# 83_SATA-SATA_PM1.net
KiCad netlist of a schematic drawn in Altium Designer
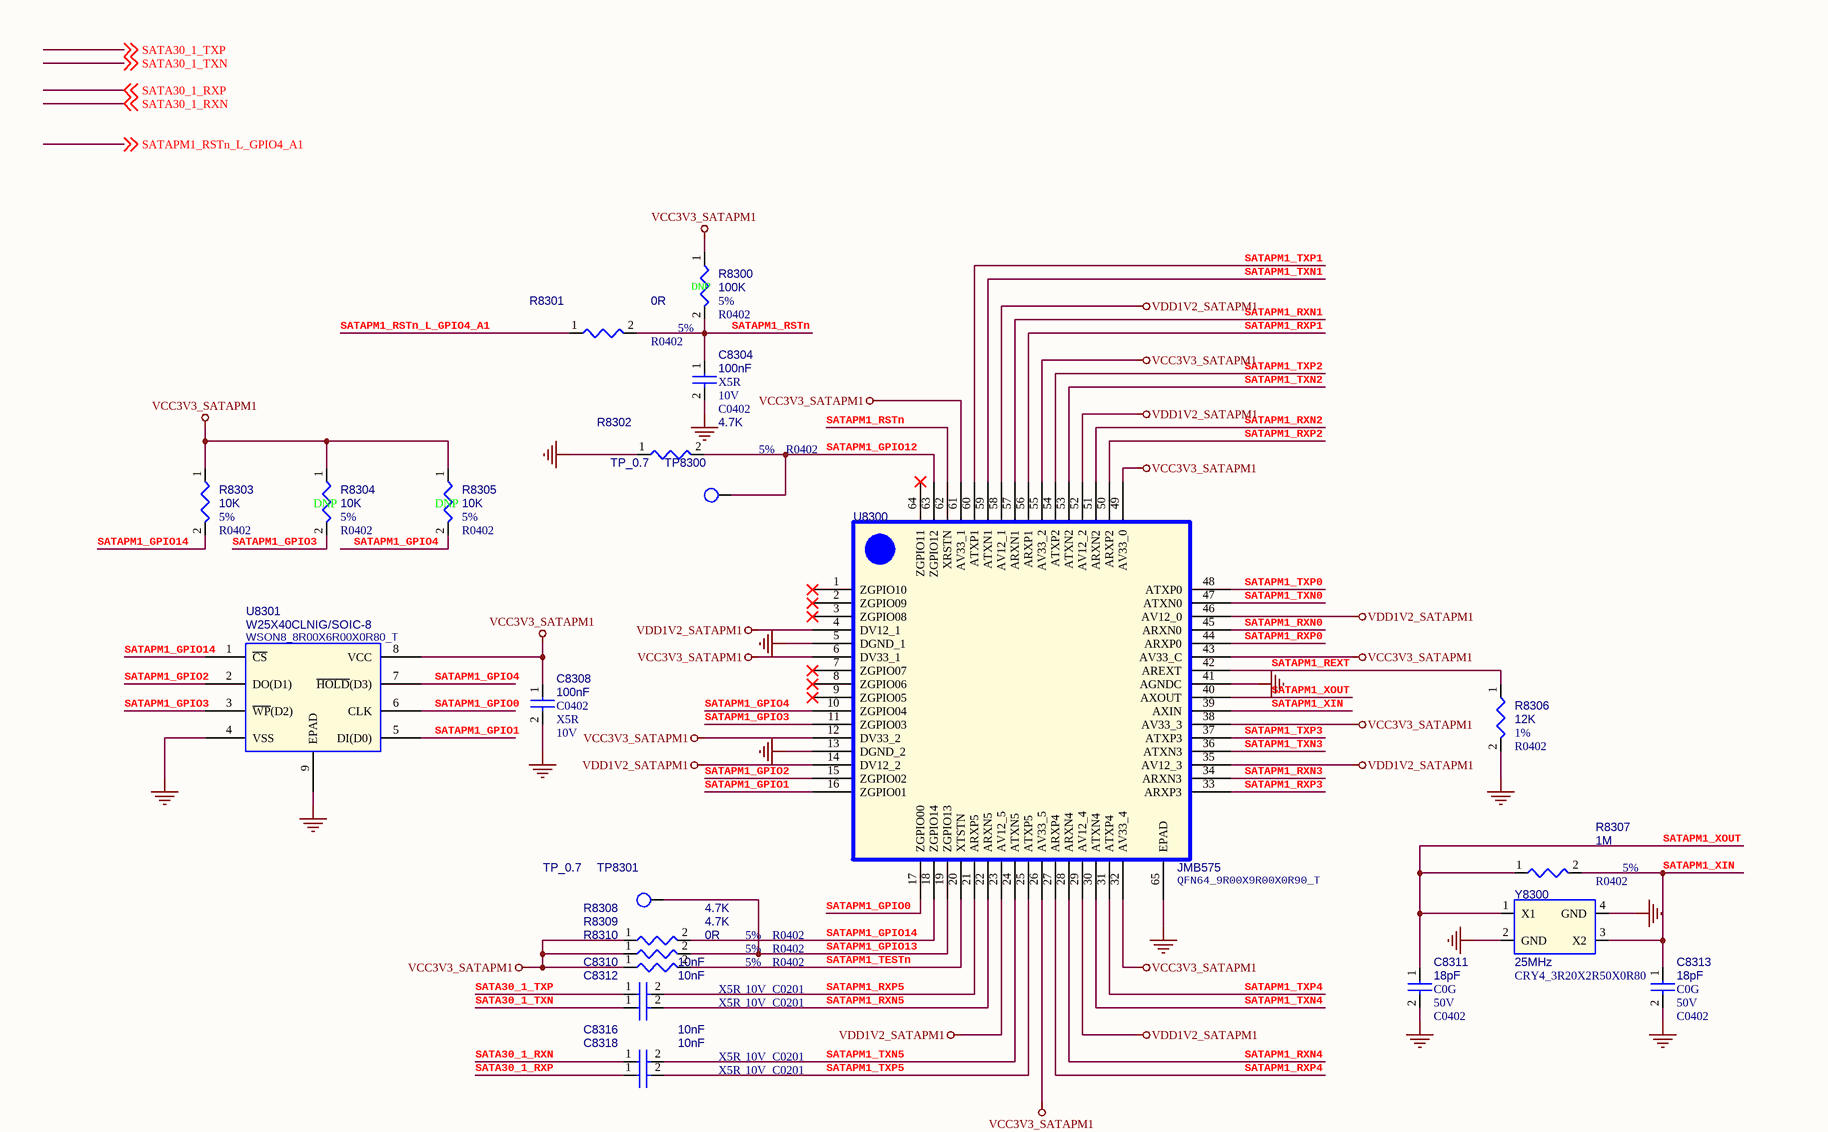
[diagram p0: 83.SATA-SATA PM1.SchDoc, top left]
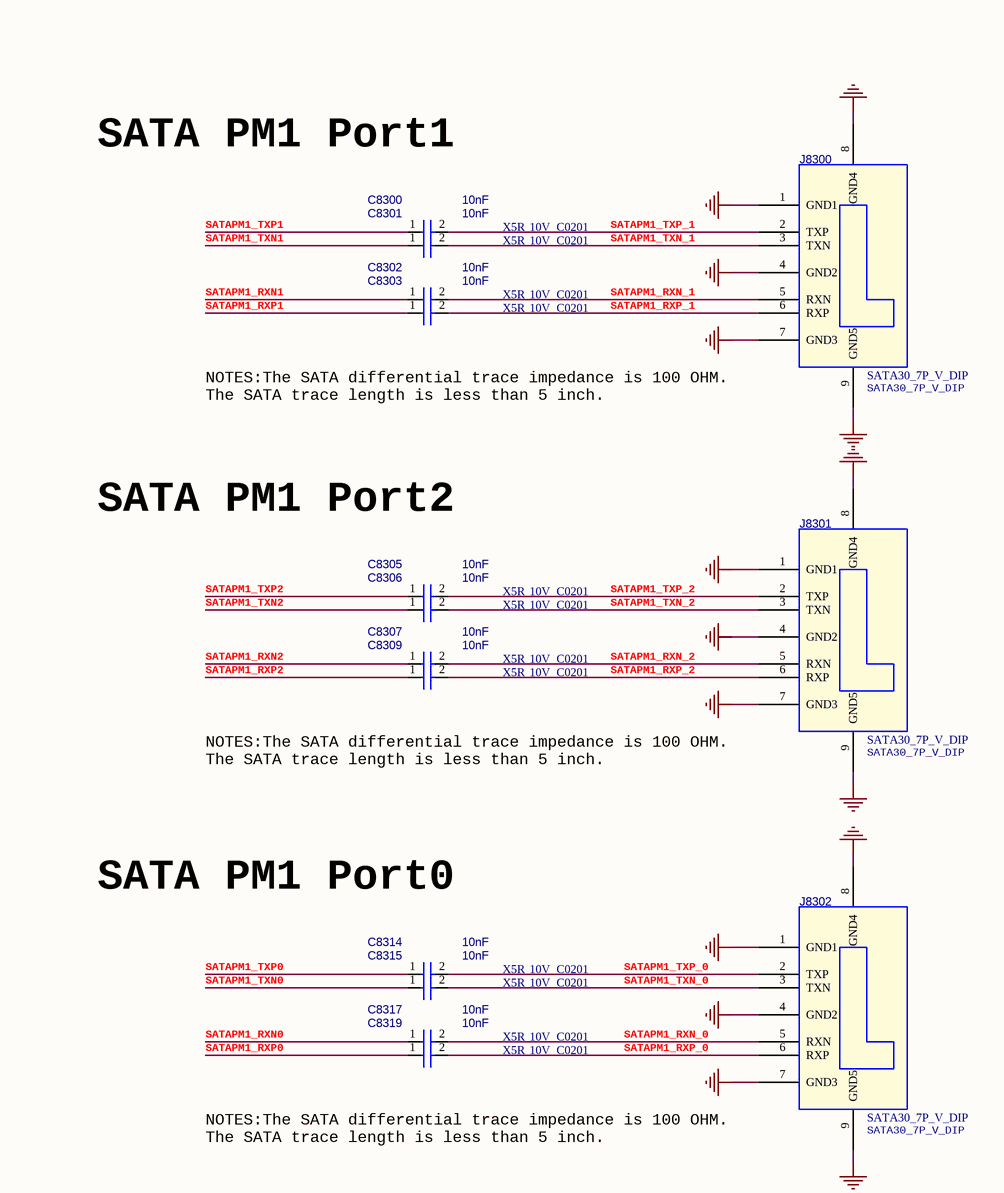
[diagram p1: 83.SATA-SATA PM1.SchDoc, top right]
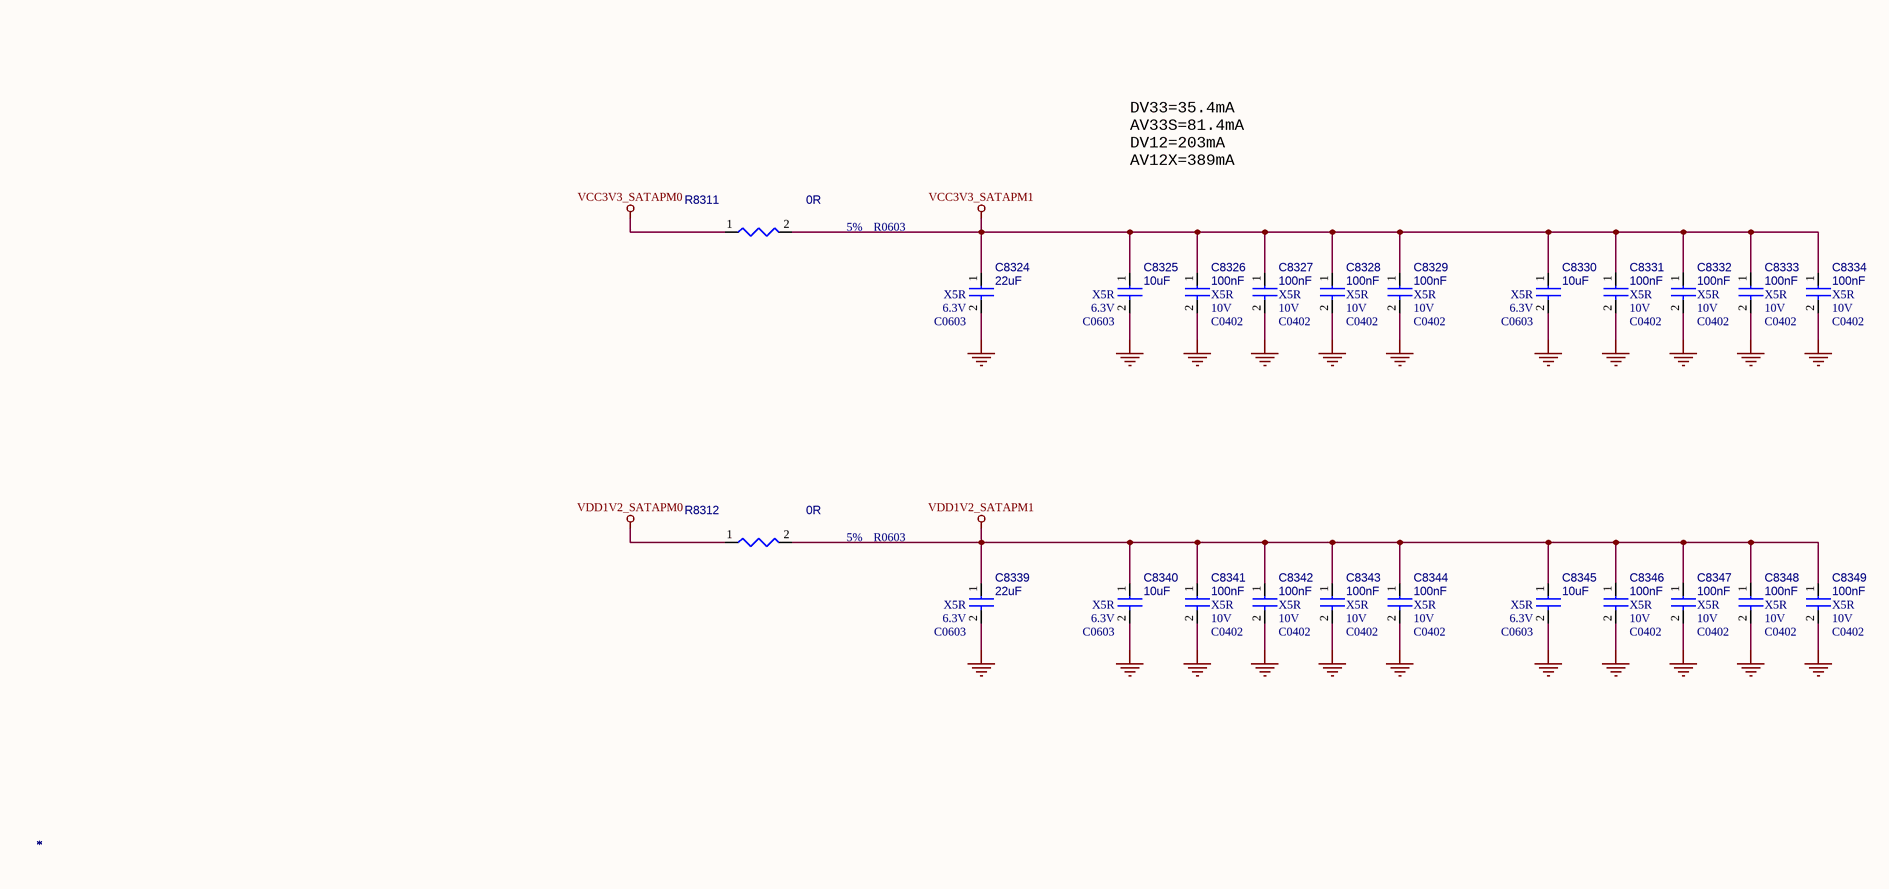
[diagram p2: 83.SATA-SATA PM1.SchDoc, bottom left]
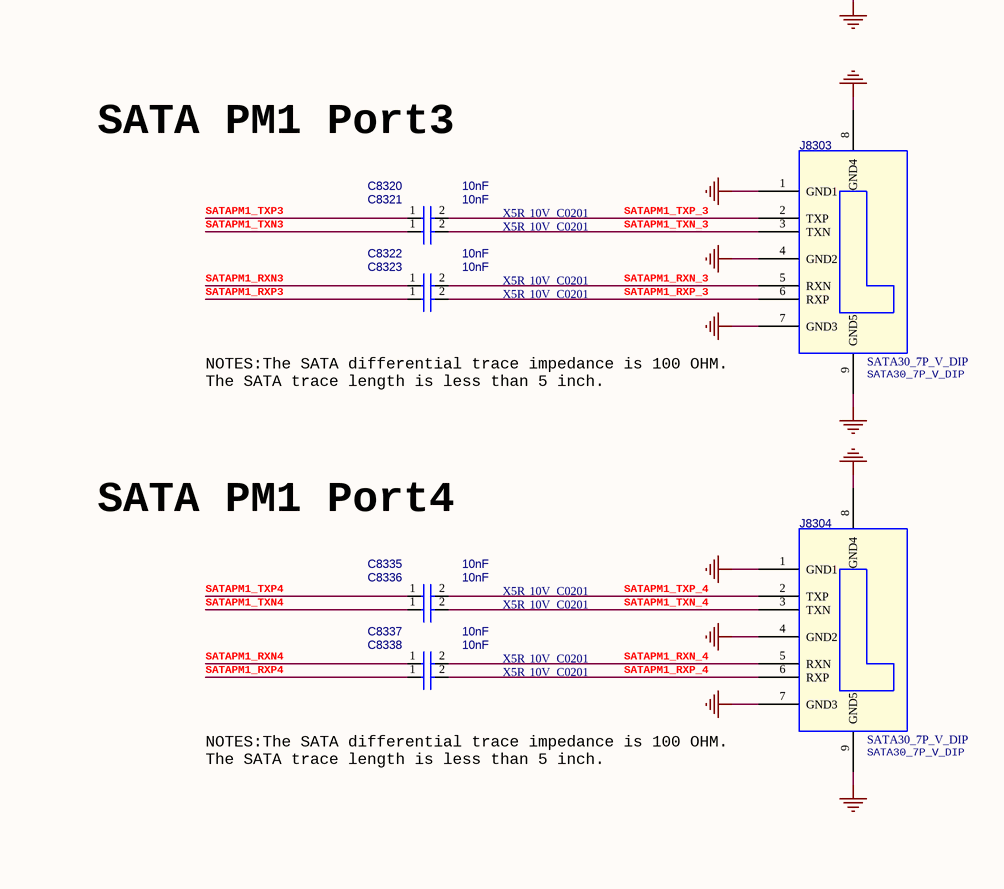
[diagram p3: 83.SATA-SATA PM1.SchDoc, bottom right]

(export (version "E")
  (design (tool "Eeschema 10.0.6"))
  (components
    (comp (ref "C8300")
      (value "*")
      (footprint "C0201")
      (description "cap,10.00nF,+/-10%,10V,X5R,C0201")
      (fields
        (field (name "VOLTAGE") "10V")
        (field (name "PCB FOOTPRINT") "C0201")
        (field (name "DIELECTRIC") "X5R")
        (field (name "MANUFACTURER") "TDK")
        (field (name "TOLERANCE") "10%")
        (field (name "ALTIUM_UNNAMED_1") "10nF")
        (field (name "CREATED BY") "JJJ")
      )
      (libsource (lib "*") (part "CAP NP"))
    )
    (comp (ref "C8301")
      (value "*")
      (footprint "C0201")
      (description "cap,10.00nF,+/-10%,10V,X5R,C0201")
      (fields
        (field (name "VOLTAGE") "10V")
        (field (name "PCB FOOTPRINT") "C0201")
        (field (name "DIELECTRIC") "X5R")
        (field (name "MANUFACTURER") "TDK")
        (field (name "TOLERANCE") "10%")
        (field (name "ALTIUM_UNNAMED_1") "10nF")
        (field (name "CREATED BY") "JJJ")
      )
      (libsource (lib "*") (part "CAP NP"))
    )
    (comp (ref "C8302")
      (value "*")
      (footprint "C0201")
      (description "cap,10.00nF,+/-10%,10V,X5R,C0201")
      (fields
        (field (name "VOLTAGE") "10V")
        (field (name "PCB FOOTPRINT") "C0201")
        (field (name "DIELECTRIC") "X5R")
        (field (name "MANUFACTURER") "TDK")
        (field (name "TOLERANCE") "10%")
        (field (name "ALTIUM_UNNAMED_1") "10nF")
        (field (name "CREATED BY") "JJJ")
      )
      (libsource (lib "*") (part "CAP NP"))
    )
    (comp (ref "C8303")
      (value "*")
      (footprint "C0201")
      (description "cap,10.00nF,+/-10%,10V,X5R,C0201")
      (fields
        (field (name "VOLTAGE") "10V")
        (field (name "PCB FOOTPRINT") "C0201")
        (field (name "DIELECTRIC") "X5R")
        (field (name "MANUFACTURER") "TDK")
        (field (name "TOLERANCE") "10%")
        (field (name "ALTIUM_UNNAMED_1") "10nF")
        (field (name "CREATED BY") "JJJ")
      )
      (libsource (lib "*") (part "CAP NP"))
    )
    (comp (ref "C8304")
      (value "*")
      (footprint "C0402")
      (description "cap,100.00nF,+/-10%,10V,X5R,C0402")
      (fields
        (field (name "VOLTAGE") "10V")
        (field (name "PCB FOOTPRINT") "C0402")
        (field (name "DIELECTRIC") "X5R")
        (field (name "TOLERANCE") "10%")
        (field (name "MANUFACTURER") "TDK")
        (field (name "ALTIUM_UNNAMED_1") "100nF")
        (field (name "CREATED BY") "JJJ")
      )
      (libsource (lib "*") (part "CAP NP"))
    )
    (comp (ref "C8305")
      (value "*")
      (footprint "C0201")
      (description "cap,10.00nF,+/-10%,10V,X5R,C0201")
      (fields
        (field (name "VOLTAGE") "10V")
        (field (name "PCB FOOTPRINT") "C0201")
        (field (name "DIELECTRIC") "X5R")
        (field (name "MANUFACTURER") "TDK")
        (field (name "TOLERANCE") "10%")
        (field (name "ALTIUM_UNNAMED_1") "10nF")
        (field (name "CREATED BY") "JJJ")
      )
      (libsource (lib "*") (part "CAP NP"))
    )
    (comp (ref "C8306")
      (value "*")
      (footprint "C0201")
      (description "cap,10.00nF,+/-10%,10V,X5R,C0201")
      (fields
        (field (name "VOLTAGE") "10V")
        (field (name "PCB FOOTPRINT") "C0201")
        (field (name "DIELECTRIC") "X5R")
        (field (name "MANUFACTURER") "TDK")
        (field (name "TOLERANCE") "10%")
        (field (name "ALTIUM_UNNAMED_1") "10nF")
        (field (name "CREATED BY") "JJJ")
      )
      (libsource (lib "*") (part "CAP NP"))
    )
    (comp (ref "C8307")
      (value "*")
      (footprint "C0201")
      (description "cap,10.00nF,+/-10%,10V,X5R,C0201")
      (fields
        (field (name "VOLTAGE") "10V")
        (field (name "PCB FOOTPRINT") "C0201")
        (field (name "DIELECTRIC") "X5R")
        (field (name "MANUFACTURER") "TDK")
        (field (name "TOLERANCE") "10%")
        (field (name "ALTIUM_UNNAMED_1") "10nF")
        (field (name "CREATED BY") "JJJ")
      )
      (libsource (lib "*") (part "CAP NP"))
    )
    (comp (ref "C8308")
      (value "*")
      (footprint "C0402")
      (description "cap,100.00nF,+/-10%,10V,X5R,C0402")
      (fields
        (field (name "VOLTAGE") "10V")
        (field (name "PCB FOOTPRINT") "C0402")
        (field (name "DIELECTRIC") "X5R")
        (field (name "TOLERANCE") "10%")
        (field (name "MANUFACTURER") "TDK")
        (field (name "ALTIUM_UNNAMED_1") "100nF")
        (field (name "CREATED BY") "JJJ")
      )
      (libsource (lib "*") (part "CAP NP"))
    )
    (comp (ref "C8309")
      (value "*")
      (footprint "C0201")
      (description "cap,10.00nF,+/-10%,10V,X5R,C0201")
      (fields
        (field (name "VOLTAGE") "10V")
        (field (name "PCB FOOTPRINT") "C0201")
        (field (name "DIELECTRIC") "X5R")
        (field (name "MANUFACTURER") "TDK")
        (field (name "TOLERANCE") "10%")
        (field (name "ALTIUM_UNNAMED_1") "10nF")
        (field (name "CREATED BY") "JJJ")
      )
      (libsource (lib "*") (part "CAP NP"))
    )
    (comp (ref "C8310")
      (value "*")
      (footprint "C0201")
      (description "cap,10.00nF,+/-10%,10V,X5R,C0201")
      (fields
        (field (name "VOLTAGE") "10V")
        (field (name "PCB FOOTPRINT") "C0201")
        (field (name "DIELECTRIC") "X5R")
        (field (name "TOLERANCE") "10%")
        (field (name "MANUFACTURER") "TDK")
        (field (name "ALTIUM_UNNAMED_1") "10nF")
        (field (name "CREATED BY") "JJJ")
      )
      (libsource (lib "*") (part "CAP NP"))
    )
    (comp (ref "C8311")
      (value "*")
      (footprint "C0402")
      (description "cap,18.00pF,+/-5%,50V,C0G,C0402")
      (fields
        (field (name "VOLTAGE") "50V")
        (field (name "PCB FOOTPRINT") "C0402")
        (field (name "DIELECTRIC") "C0G")
        (field (name "TOLERANCE") "5%")
        (field (name "MANUFACTURER") "TDK")
        (field (name "ALTIUM_UNNAMED_1") "18pF")
        (field (name "CREATED BY") "JJJ")
      )
      (libsource (lib "*") (part "CAP NP"))
    )
    (comp (ref "C8312")
      (value "*")
      (footprint "C0201")
      (description "cap,10.00nF,+/-10%,10V,X5R,C0201")
      (fields
        (field (name "VOLTAGE") "10V")
        (field (name "PCB FOOTPRINT") "C0201")
        (field (name "DIELECTRIC") "X5R")
        (field (name "TOLERANCE") "10%")
        (field (name "MANUFACTURER") "TDK")
        (field (name "ALTIUM_UNNAMED_1") "10nF")
        (field (name "CREATED BY") "JJJ")
      )
      (libsource (lib "*") (part "CAP NP"))
    )
    (comp (ref "C8313")
      (value "*")
      (footprint "C0402")
      (description "cap,18.00pF,+/-5%,50V,C0G,C0402")
      (fields
        (field (name "VOLTAGE") "50V")
        (field (name "PCB FOOTPRINT") "C0402")
        (field (name "DIELECTRIC") "C0G")
        (field (name "TOLERANCE") "5%")
        (field (name "MANUFACTURER") "TDK")
        (field (name "ALTIUM_UNNAMED_1") "18pF")
        (field (name "CREATED BY") "JJJ")
      )
      (libsource (lib "*") (part "CAP NP"))
    )
    (comp (ref "C8314")
      (value "*")
      (footprint "C0201")
      (description "cap,10.00nF,+/-10%,10V,X5R,C0201")
      (fields
        (field (name "VOLTAGE") "10V")
        (field (name "PCB FOOTPRINT") "C0201")
        (field (name "DIELECTRIC") "X5R")
        (field (name "MANUFACTURER") "TDK")
        (field (name "TOLERANCE") "10%")
        (field (name "ALTIUM_UNNAMED_1") "10nF")
        (field (name "CREATED BY") "JJJ")
      )
      (libsource (lib "*") (part "CAP NP"))
    )
    (comp (ref "C8315")
      (value "*")
      (footprint "C0201")
      (description "cap,10.00nF,+/-10%,10V,X5R,C0201")
      (fields
        (field (name "VOLTAGE") "10V")
        (field (name "PCB FOOTPRINT") "C0201")
        (field (name "DIELECTRIC") "X5R")
        (field (name "MANUFACTURER") "TDK")
        (field (name "TOLERANCE") "10%")
        (field (name "ALTIUM_UNNAMED_1") "10nF")
        (field (name "CREATED BY") "JJJ")
      )
      (libsource (lib "*") (part "CAP NP"))
    )
    (comp (ref "C8316")
      (value "*")
      (footprint "C0201")
      (description "cap,10.00nF,+/-10%,10V,X5R,C0201")
      (fields
        (field (name "VOLTAGE") "10V")
        (field (name "PCB FOOTPRINT") "C0201")
        (field (name "DIELECTRIC") "X5R")
        (field (name "TOLERANCE") "10%")
        (field (name "MANUFACTURER") "TDK")
        (field (name "ALTIUM_UNNAMED_1") "10nF")
        (field (name "CREATED BY") "JJJ")
      )
      (libsource (lib "*") (part "CAP NP"))
    )
    (comp (ref "C8317")
      (value "*")
      (footprint "C0201")
      (description "cap,10.00nF,+/-10%,10V,X5R,C0201")
      (fields
        (field (name "VOLTAGE") "10V")
        (field (name "PCB FOOTPRINT") "C0201")
        (field (name "DIELECTRIC") "X5R")
        (field (name "MANUFACTURER") "TDK")
        (field (name "TOLERANCE") "10%")
        (field (name "ALTIUM_UNNAMED_1") "10nF")
        (field (name "CREATED BY") "JJJ")
      )
      (libsource (lib "*") (part "CAP NP"))
    )
    (comp (ref "C8318")
      (value "*")
      (footprint "C0201")
      (description "cap,10.00nF,+/-10%,10V,X5R,C0201")
      (fields
        (field (name "VOLTAGE") "10V")
        (field (name "PCB FOOTPRINT") "C0201")
        (field (name "DIELECTRIC") "X5R")
        (field (name "TOLERANCE") "10%")
        (field (name "MANUFACTURER") "TDK")
        (field (name "ALTIUM_UNNAMED_1") "10nF")
        (field (name "CREATED BY") "JJJ")
      )
      (libsource (lib "*") (part "CAP NP"))
    )
    (comp (ref "C8319")
      (value "*")
      (footprint "C0201")
      (description "cap,10.00nF,+/-10%,10V,X5R,C0201")
      (fields
        (field (name "VOLTAGE") "10V")
        (field (name "PCB FOOTPRINT") "C0201")
        (field (name "DIELECTRIC") "X5R")
        (field (name "MANUFACTURER") "TDK")
        (field (name "TOLERANCE") "10%")
        (field (name "ALTIUM_UNNAMED_1") "10nF")
        (field (name "CREATED BY") "JJJ")
      )
      (libsource (lib "*") (part "CAP NP"))
    )
    (comp (ref "C8320")
      (value "*")
      (footprint "C0201")
      (description "cap,10.00nF,+/-10%,10V,X5R,C0201")
      (fields
        (field (name "VOLTAGE") "10V")
        (field (name "PCB FOOTPRINT") "C0201")
        (field (name "DIELECTRIC") "X5R")
        (field (name "MANUFACTURER") "TDK")
        (field (name "TOLERANCE") "10%")
        (field (name "ALTIUM_UNNAMED_1") "10nF")
        (field (name "CREATED BY") "JJJ")
      )
      (libsource (lib "*") (part "CAP NP"))
    )
    (comp (ref "C8321")
      (value "*")
      (footprint "C0201")
      (description "cap,10.00nF,+/-10%,10V,X5R,C0201")
      (fields
        (field (name "VOLTAGE") "10V")
        (field (name "PCB FOOTPRINT") "C0201")
        (field (name "DIELECTRIC") "X5R")
        (field (name "MANUFACTURER") "TDK")
        (field (name "TOLERANCE") "10%")
        (field (name "ALTIUM_UNNAMED_1") "10nF")
        (field (name "CREATED BY") "JJJ")
      )
      (libsource (lib "*") (part "CAP NP"))
    )
    (comp (ref "C8322")
      (value "*")
      (footprint "C0201")
      (description "cap,10.00nF,+/-10%,10V,X5R,C0201")
      (fields
        (field (name "VOLTAGE") "10V")
        (field (name "PCB FOOTPRINT") "C0201")
        (field (name "DIELECTRIC") "X5R")
        (field (name "MANUFACTURER") "TDK")
        (field (name "TOLERANCE") "10%")
        (field (name "ALTIUM_UNNAMED_1") "10nF")
        (field (name "CREATED BY") "JJJ")
      )
      (libsource (lib "*") (part "CAP NP"))
    )
    (comp (ref "C8323")
      (value "*")
      (footprint "C0201")
      (description "cap,10.00nF,+/-10%,10V,X5R,C0201")
      (fields
        (field (name "VOLTAGE") "10V")
        (field (name "PCB FOOTPRINT") "C0201")
        (field (name "DIELECTRIC") "X5R")
        (field (name "MANUFACTURER") "TDK")
        (field (name "TOLERANCE") "10%")
        (field (name "ALTIUM_UNNAMED_1") "10nF")
        (field (name "CREATED BY") "JJJ")
      )
      (libsource (lib "*") (part "CAP NP"))
    )
    (comp (ref "C8324")
      (value "*")
      (footprint "C0603")
      (description "cap,22.00uF,+/-20%,6.3V,X5R,C0603")
      (fields
        (field (name "VOLTAGE") "6.3V")
        (field (name "PCB FOOTPRINT") "C0603")
        (field (name "DIELECTRIC") "X5R")
        (field (name "MANUFACTURER") "TDK")
        (field (name "TOLERANCE") "20%")
        (field (name "ALTIUM_UNNAMED_1") "22uF")
        (field (name "CREATED BY") "JJJ")
      )
      (libsource (lib "*") (part "CAP NP"))
    )
    (comp (ref "C8325")
      (value "*")
      (footprint "C0603")
      (description "cap,10.00uF,+/-10%,6.3V,X5R,C0603")
      (fields
        (field (name "VOLTAGE") "6.3V")
        (field (name "PCB FOOTPRINT") "C0603")
        (field (name "DIELECTRIC") "X5R")
        (field (name "TOLERANCE") "10%")
        (field (name "MANUFACTURER") "TDK")
        (field (name "ALTIUM_UNNAMED_1") "10uF")
        (field (name "CREATED BY") "JJJ")
      )
      (libsource (lib "*") (part "CAP NP"))
    )
    (comp (ref "C8326")
      (value "*")
      (footprint "C0402")
      (description "cap,100.00nF,+/-10%,10V,X5R,C0402")
      (fields
        (field (name "VOLTAGE") "10V")
        (field (name "PCB FOOTPRINT") "C0402")
        (field (name "DIELECTRIC") "X5R")
        (field (name "MANUFACTURER") "TDK")
        (field (name "TOLERANCE") "10%")
        (field (name "ALTIUM_UNNAMED_1") "100nF")
        (field (name "CREATED BY") "JJJ")
      )
      (libsource (lib "*") (part "CAP NP"))
    )
    (comp (ref "C8327")
      (value "*")
      (footprint "C0402")
      (description "cap,100.00nF,+/-10%,10V,X5R,C0402")
      (fields
        (field (name "VOLTAGE") "10V")
        (field (name "PCB FOOTPRINT") "C0402")
        (field (name "DIELECTRIC") "X5R")
        (field (name "MANUFACTURER") "TDK")
        (field (name "TOLERANCE") "10%")
        (field (name "ALTIUM_UNNAMED_1") "100nF")
        (field (name "CREATED BY") "JJJ")
      )
      (libsource (lib "*") (part "CAP NP"))
    )
    (comp (ref "C8328")
      (value "*")
      (footprint "C0402")
      (description "cap,100.00nF,+/-10%,10V,X5R,C0402")
      (fields
        (field (name "VOLTAGE") "10V")
        (field (name "PCB FOOTPRINT") "C0402")
        (field (name "DIELECTRIC") "X5R")
        (field (name "MANUFACTURER") "TDK")
        (field (name "TOLERANCE") "10%")
        (field (name "ALTIUM_UNNAMED_1") "100nF")
        (field (name "CREATED BY") "JJJ")
      )
      (libsource (lib "*") (part "CAP NP"))
    )
    (comp (ref "C8329")
      (value "*")
      (footprint "C0402")
      (description "cap,100.00nF,+/-10%,10V,X5R,C0402")
      (fields
        (field (name "VOLTAGE") "10V")
        (field (name "PCB FOOTPRINT") "C0402")
        (field (name "DIELECTRIC") "X5R")
        (field (name "MANUFACTURER") "TDK")
        (field (name "TOLERANCE") "10%")
        (field (name "ALTIUM_UNNAMED_1") "100nF")
        (field (name "CREATED BY") "JJJ")
      )
      (libsource (lib "*") (part "CAP NP"))
    )
    (comp (ref "C8330")
      (value "*")
      (footprint "C0603")
      (description "cap,10.00uF,+/-10%,6.3V,X5R,C0603")
      (fields
        (field (name "VOLTAGE") "6.3V")
        (field (name "PCB FOOTPRINT") "C0603")
        (field (name "DIELECTRIC") "X5R")
        (field (name "TOLERANCE") "10%")
        (field (name "MANUFACTURER") "TDK")
        (field (name "ALTIUM_UNNAMED_1") "10uF")
        (field (name "CREATED BY") "JJJ")
      )
      (libsource (lib "*") (part "CAP NP"))
    )
    (comp (ref "C8331")
      (value "*")
      (footprint "C0402")
      (description "cap,100.00nF,+/-10%,10V,X5R,C0402")
      (fields
        (field (name "VOLTAGE") "10V")
        (field (name "PCB FOOTPRINT") "C0402")
        (field (name "DIELECTRIC") "X5R")
        (field (name "MANUFACTURER") "TDK")
        (field (name "TOLERANCE") "10%")
        (field (name "ALTIUM_UNNAMED_1") "100nF")
        (field (name "CREATED BY") "JJJ")
      )
      (libsource (lib "*") (part "CAP NP"))
    )
    (comp (ref "C8332")
      (value "*")
      (footprint "C0402")
      (description "cap,100.00nF,+/-10%,10V,X5R,C0402")
      (fields
        (field (name "VOLTAGE") "10V")
        (field (name "PCB FOOTPRINT") "C0402")
        (field (name "DIELECTRIC") "X5R")
        (field (name "MANUFACTURER") "TDK")
        (field (name "TOLERANCE") "10%")
        (field (name "ALTIUM_UNNAMED_1") "100nF")
        (field (name "CREATED BY") "JJJ")
      )
      (libsource (lib "*") (part "CAP NP"))
    )
    (comp (ref "C8333")
      (value "*")
      (footprint "C0402")
      (description "cap,100.00nF,+/-10%,10V,X5R,C0402")
      (fields
        (field (name "VOLTAGE") "10V")
        (field (name "PCB FOOTPRINT") "C0402")
        (field (name "DIELECTRIC") "X5R")
        (field (name "MANUFACTURER") "TDK")
        (field (name "TOLERANCE") "10%")
        (field (name "ALTIUM_UNNAMED_1") "100nF")
        (field (name "CREATED BY") "JJJ")
      )
      (libsource (lib "*") (part "CAP NP"))
    )
    (comp (ref "C8334")
      (value "*")
      (footprint "C0402")
      (description "cap,100.00nF,+/-10%,10V,X5R,C0402")
      (fields
        (field (name "VOLTAGE") "10V")
        (field (name "PCB FOOTPRINT") "C0402")
        (field (name "DIELECTRIC") "X5R")
        (field (name "MANUFACTURER") "TDK")
        (field (name "TOLERANCE") "10%")
        (field (name "ALTIUM_UNNAMED_1") "100nF")
        (field (name "CREATED BY") "JJJ")
      )
      (libsource (lib "*") (part "CAP NP"))
    )
    (comp (ref "C8335")
      (value "*")
      (footprint "C0201")
      (description "cap,10.00nF,+/-10%,10V,X5R,C0201")
      (fields
        (field (name "VOLTAGE") "10V")
        (field (name "PCB FOOTPRINT") "C0201")
        (field (name "DIELECTRIC") "X5R")
        (field (name "MANUFACTURER") "TDK")
        (field (name "TOLERANCE") "10%")
        (field (name "ALTIUM_UNNAMED_1") "10nF")
        (field (name "CREATED BY") "JJJ")
      )
      (libsource (lib "*") (part "CAP NP"))
    )
    (comp (ref "C8336")
      (value "*")
      (footprint "C0201")
      (description "cap,10.00nF,+/-10%,10V,X5R,C0201")
      (fields
        (field (name "VOLTAGE") "10V")
        (field (name "PCB FOOTPRINT") "C0201")
        (field (name "DIELECTRIC") "X5R")
        (field (name "MANUFACTURER") "TDK")
        (field (name "TOLERANCE") "10%")
        (field (name "ALTIUM_UNNAMED_1") "10nF")
        (field (name "CREATED BY") "JJJ")
      )
      (libsource (lib "*") (part "CAP NP"))
    )
    (comp (ref "C8337")
      (value "*")
      (footprint "C0201")
      (description "cap,10.00nF,+/-10%,10V,X5R,C0201")
      (fields
        (field (name "VOLTAGE") "10V")
        (field (name "PCB FOOTPRINT") "C0201")
        (field (name "DIELECTRIC") "X5R")
        (field (name "MANUFACTURER") "TDK")
        (field (name "TOLERANCE") "10%")
        (field (name "ALTIUM_UNNAMED_1") "10nF")
        (field (name "CREATED BY") "JJJ")
      )
      (libsource (lib "*") (part "CAP NP"))
    )
    (comp (ref "C8338")
      (value "*")
      (footprint "C0201")
      (description "cap,10.00nF,+/-10%,10V,X5R,C0201")
      (fields
        (field (name "VOLTAGE") "10V")
        (field (name "PCB FOOTPRINT") "C0201")
        (field (name "DIELECTRIC") "X5R")
        (field (name "MANUFACTURER") "TDK")
        (field (name "TOLERANCE") "10%")
        (field (name "ALTIUM_UNNAMED_1") "10nF")
        (field (name "CREATED BY") "JJJ")
      )
      (libsource (lib "*") (part "CAP NP"))
    )
    (comp (ref "C8339")
      (value "*")
      (footprint "C0603")
      (description "cap,22.00uF,+/-20%,6.3V,X5R,C0603")
      (fields
        (field (name "VOLTAGE") "6.3V")
        (field (name "PCB FOOTPRINT") "C0603")
        (field (name "DIELECTRIC") "X5R")
        (field (name "TOLERANCE") "20%")
        (field (name "MANUFACTURER") "TDK")
        (field (name "ALTIUM_UNNAMED_1") "22uF")
        (field (name "CREATED BY") "JJJ")
      )
      (libsource (lib "*") (part "CAP NP"))
    )
    (comp (ref "C8340")
      (value "*")
      (footprint "C0603")
      (description "cap,10.00uF,+/-10%,6.3V,X5R,C0603")
      (fields
        (field (name "VOLTAGE") "6.3V")
        (field (name "PCB FOOTPRINT") "C0603")
        (field (name "DIELECTRIC") "X5R")
        (field (name "TOLERANCE") "10%")
        (field (name "MANUFACTURER") "TDK")
        (field (name "ALTIUM_UNNAMED_1") "10uF")
        (field (name "CREATED BY") "JJJ")
      )
      (libsource (lib "*") (part "CAP NP"))
    )
    (comp (ref "C8341")
      (value "*")
      (footprint "C0402")
      (description "cap,100.00nF,+/-10%,10V,X5R,C0402")
      (fields
        (field (name "VOLTAGE") "10V")
        (field (name "PCB FOOTPRINT") "C0402")
        (field (name "DIELECTRIC") "X5R")
        (field (name "MANUFACTURER") "TDK")
        (field (name "TOLERANCE") "10%")
        (field (name "ALTIUM_UNNAMED_1") "100nF")
        (field (name "CREATED BY") "JJJ")
      )
      (libsource (lib "*") (part "CAP NP"))
    )
    (comp (ref "C8342")
      (value "*")
      (footprint "C0402")
      (description "cap,100.00nF,+/-10%,10V,X5R,C0402")
      (fields
        (field (name "VOLTAGE") "10V")
        (field (name "PCB FOOTPRINT") "C0402")
        (field (name "DIELECTRIC") "X5R")
        (field (name "MANUFACTURER") "TDK")
        (field (name "TOLERANCE") "10%")
        (field (name "ALTIUM_UNNAMED_1") "100nF")
        (field (name "CREATED BY") "JJJ")
      )
      (libsource (lib "*") (part "CAP NP"))
    )
    (comp (ref "C8343")
      (value "*")
      (footprint "C0402")
      (description "cap,100.00nF,+/-10%,10V,X5R,C0402")
      (fields
        (field (name "VOLTAGE") "10V")
        (field (name "PCB FOOTPRINT") "C0402")
        (field (name "DIELECTRIC") "X5R")
        (field (name "MANUFACTURER") "TDK")
        (field (name "TOLERANCE") "10%")
        (field (name "ALTIUM_UNNAMED_1") "100nF")
        (field (name "CREATED BY") "JJJ")
      )
      (libsource (lib "*") (part "CAP NP"))
    )
    (comp (ref "C8344")
      (value "*")
      (footprint "C0402")
      (description "cap,100.00nF,+/-10%,10V,X5R,C0402")
      (fields
        (field (name "VOLTAGE") "10V")
        (field (name "PCB FOOTPRINT") "C0402")
        (field (name "DIELECTRIC") "X5R")
        (field (name "MANUFACTURER") "TDK")
        (field (name "TOLERANCE") "10%")
        (field (name "ALTIUM_UNNAMED_1") "100nF")
        (field (name "CREATED BY") "JJJ")
      )
      (libsource (lib "*") (part "CAP NP"))
    )
    (comp (ref "C8345")
      (value "*")
      (footprint "C0603")
      (description "cap,10.00uF,+/-10%,6.3V,X5R,C0603")
      (fields
        (field (name "VOLTAGE") "6.3V")
        (field (name "PCB FOOTPRINT") "C0603")
        (field (name "DIELECTRIC") "X5R")
        (field (name "TOLERANCE") "10%")
        (field (name "MANUFACTURER") "TDK")
        (field (name "ALTIUM_UNNAMED_1") "10uF")
        (field (name "CREATED BY") "JJJ")
      )
      (libsource (lib "*") (part "CAP NP"))
    )
    (comp (ref "C8346")
      (value "*")
      (footprint "C0402")
      (description "cap,100.00nF,+/-10%,10V,X5R,C0402")
      (fields
        (field (name "VOLTAGE") "10V")
        (field (name "PCB FOOTPRINT") "C0402")
        (field (name "DIELECTRIC") "X5R")
        (field (name "MANUFACTURER") "TDK")
        (field (name "TOLERANCE") "10%")
        (field (name "ALTIUM_UNNAMED_1") "100nF")
        (field (name "CREATED BY") "JJJ")
      )
      (libsource (lib "*") (part "CAP NP"))
    )
    (comp (ref "C8347")
      (value "*")
      (footprint "C0402")
      (description "cap,100.00nF,+/-10%,10V,X5R,C0402")
      (fields
        (field (name "VOLTAGE") "10V")
        (field (name "PCB FOOTPRINT") "C0402")
        (field (name "DIELECTRIC") "X5R")
        (field (name "MANUFACTURER") "TDK")
        (field (name "TOLERANCE") "10%")
        (field (name "ALTIUM_UNNAMED_1") "100nF")
        (field (name "CREATED BY") "JJJ")
      )
      (libsource (lib "*") (part "CAP NP"))
    )
    (comp (ref "C8348")
      (value "*")
      (footprint "C0402")
      (description "cap,100.00nF,+/-10%,10V,X5R,C0402")
      (fields
        (field (name "VOLTAGE") "10V")
        (field (name "PCB FOOTPRINT") "C0402")
        (field (name "DIELECTRIC") "X5R")
        (field (name "MANUFACTURER") "TDK")
        (field (name "TOLERANCE") "10%")
        (field (name "ALTIUM_UNNAMED_1") "100nF")
        (field (name "CREATED BY") "JJJ")
      )
      (libsource (lib "*") (part "CAP NP"))
    )
    (comp (ref "C8349")
      (value "*")
      (footprint "C0402")
      (description "cap,100.00nF,+/-10%,10V,X5R,C0402")
      (fields
        (field (name "VOLTAGE") "10V")
        (field (name "PCB FOOTPRINT") "C0402")
        (field (name "DIELECTRIC") "X5R")
        (field (name "MANUFACTURER") "TDK")
        (field (name "TOLERANCE") "10%")
        (field (name "ALTIUM_UNNAMED_1") "100nF")
        (field (name "CREATED BY") "JJJ")
      )
      (libsource (lib "*") (part "CAP NP"))
    )
    (comp (ref "J8300")
      (value "*")
      (footprint "SATA30_7P_V_DIP")
      (fields
        (field (name "PCB FOOTPRINT") "SATA30_7P_V_DIP")
        (field (name "ALTIUM_UNNAMED_1") "SATA30_7P_V_DIP")
      )
      (libsource (lib "*") (part "SATA_DIP_0"))
    )
    (comp (ref "J8301")
      (value "*")
      (footprint "SATA30_7P_V_DIP")
      (fields
        (field (name "PCB FOOTPRINT") "SATA30_7P_V_DIP")
        (field (name "ALTIUM_UNNAMED_1") "SATA30_7P_V_DIP")
      )
      (libsource (lib "*") (part "SATA_DIP_0"))
    )
    (comp (ref "J8302")
      (value "*")
      (footprint "SATA30_7P_V_DIP")
      (fields
        (field (name "PCB FOOTPRINT") "SATA30_7P_V_DIP")
        (field (name "ALTIUM_UNNAMED_1") "SATA30_7P_V_DIP")
      )
      (libsource (lib "*") (part "SATA_DIP_0"))
    )
    (comp (ref "J8303")
      (value "*")
      (footprint "SATA30_7P_V_DIP")
      (fields
        (field (name "PCB FOOTPRINT") "SATA30_7P_V_DIP")
        (field (name "ALTIUM_UNNAMED_1") "SATA30_7P_V_DIP")
      )
      (libsource (lib "*") (part "SATA_DIP_0"))
    )
    (comp (ref "J8304")
      (value "*")
      (footprint "SATA30_7P_V_DIP")
      (fields
        (field (name "PCB FOOTPRINT") "SATA30_7P_V_DIP")
        (field (name "ALTIUM_UNNAMED_1") "SATA30_7P_V_DIP")
      )
      (libsource (lib "*") (part "SATA_DIP_0"))
    )
    (comp (ref "R8300")
      (value "*")
      (footprint "R0402")
      (description "НЁУГєсД¤µзЧи,100K,+/-5%,R0402,1/16W.")
      (fields
        (field (name "PCB FOOTPRINT") "R0402")
        (field (name "TOLERANCE") "5%")
        (field (name "MANUFACTURER") "YAGEO")
        (field (name "OPTION") "DNP")
        (field (name "ALTIUM_UNNAMED_1") "100K")
        (field (name "CREATED BY") "YTL")
      )
      (libsource (lib "*") (part "RESISTOR_Dup1"))
    )
    (comp (ref "R8301")
      (value "*")
      (footprint "R0402")
      (description "НЁУГєсД¤µзЧи,0R,+/-5%,R0402,1/16W.")
      (fields
        (field (name "PCB FOOTPRINT") "R0402")
        (field (name "TOLERANCE") "5%")
        (field (name "MANUFACTURER") "YAGEO")
        (field (name "ALTIUM_UNNAMED_1") "0R")
        (field (name "CREATED BY") "YTL")
      )
      (libsource (lib "*") (part "RESISTOR_Dup1"))
    )
    (comp (ref "R8302")
      (value "*")
      (footprint "R0402")
      (description "НЁУГєсД¤µзЧи,4K7,+/-5%,R0402,1/16W.")
      (fields
        (field (name "PCB FOOTPRINT") "R0402")
        (field (name "TOLERANCE") "5%")
        (field (name "MANUFACTURER") "YAGEO")
        (field (name "ALTIUM_UNNAMED_1") "4.7K")
        (field (name "CREATED BY") "YTL")
      )
      (libsource (lib "*") (part "RESISTOR_Dup1"))
    )
    (comp (ref "R8303")
      (value "*")
      (footprint "R0402")
      (description "НЁУГєсД¤µзЧи,10K,+/-5%,R0402,1/16W.")
      (fields
        (field (name "PCB FOOTPRINT") "R0402")
        (field (name "TOLERANCE") "5%")
        (field (name "MANUFACTURER") "YAGEO")
        (field (name "ALTIUM_UNNAMED_1") "10K")
        (field (name "CREATED BY") "YTL")
      )
      (libsource (lib "*") (part "RESISTOR_Dup1"))
    )
    (comp (ref "R8304")
      (value "*")
      (footprint "R0402")
      (description "НЁУГєсД¤µзЧи,10K,+/-5%,R0402,1/16W.")
      (fields
        (field (name "PCB FOOTPRINT") "R0402")
        (field (name "TOLERANCE") "5%")
        (field (name "OPTION") "DNP")
        (field (name "MANUFACTURER") "YAGEO")
        (field (name "ALTIUM_UNNAMED_1") "10K")
        (field (name "CREATED BY") "YTL")
      )
      (libsource (lib "*") (part "RESISTOR_Dup1"))
    )
    (comp (ref "R8305")
      (value "*")
      (footprint "R0402")
      (description "НЁУГєсД¤µзЧи,10K,+/-5%,R0402,1/16W.")
      (fields
        (field (name "PCB FOOTPRINT") "R0402")
        (field (name "TOLERANCE") "5%")
        (field (name "OPTION") "DNP")
        (field (name "MANUFACTURER") "YAGEO")
        (field (name "ALTIUM_UNNAMED_1") "10K")
        (field (name "CREATED BY") "YTL")
      )
      (libsource (lib "*") (part "RESISTOR_Dup1"))
    )
    (comp (ref "R8306")
      (value "*")
      (footprint "R0402")
      (description "НЁУГєсД¤µзЧи,12K,+/-1%,R0402,1/16W.")
      (fields
        (field (name "PCB FOOTPRINT") "R0402")
        (field (name "TOLERANCE") "1%")
        (field (name "MANUFACTURER") "YAGEO")
        (field (name "ALTIUM_UNNAMED_1") "12K")
        (field (name "CREATED BY") "YTL")
      )
      (libsource (lib "*") (part "RESISTOR_Dup1"))
    )
    (comp (ref "R8307")
      (value "*")
      (footprint "R0402")
      (description "НЁУГєсД¤µзЧи,1M,+/-5%,R0402,1/16W.")
      (fields
        (field (name "PCB FOOTPRINT") "R0402")
        (field (name "TOLERANCE") "5%")
        (field (name "MANUFACTURER") "YAGEO")
        (field (name "ALTIUM_UNNAMED_1") "1M")
        (field (name "CREATED BY") "YTL")
      )
      (libsource (lib "*") (part "RESISTOR_Dup1"))
    )
    (comp (ref "R8308")
      (value "*")
      (footprint "R0402")
      (description "НЁУГєсД¤µзЧи,4K7,+/-5%,R0402,1/16W.")
      (fields
        (field (name "PCB FOOTPRINT") "R0402")
        (field (name "TOLERANCE") "5%")
        (field (name "MANUFACTURER") "YAGEO")
        (field (name "ALTIUM_UNNAMED_1") "4.7K")
        (field (name "CREATED BY") "YTL")
      )
      (libsource (lib "*") (part "RESISTOR_Dup1"))
    )
    (comp (ref "R8309")
      (value "*")
      (footprint "R0402")
      (description "НЁУГєсД¤µзЧи,4K7,+/-5%,R0402,1/16W.")
      (fields
        (field (name "PCB FOOTPRINT") "R0402")
        (field (name "TOLERANCE") "5%")
        (field (name "MANUFACTURER") "YAGEO")
        (field (name "ALTIUM_UNNAMED_1") "4.7K")
        (field (name "CREATED BY") "YTL")
      )
      (libsource (lib "*") (part "RESISTOR_Dup1"))
    )
    (comp (ref "R8310")
      (value "*")
      (footprint "R0402")
      (description "НЁУГєсД¤µзЧи,0R,+/-5%,R0402,1/16W.")
      (fields
        (field (name "PCB FOOTPRINT") "R0402")
        (field (name "TOLERANCE") "5%")
        (field (name "MANUFACTURER") "YAGEO")
        (field (name "ALTIUM_UNNAMED_1") "0R")
        (field (name "CREATED BY") "YTL")
      )
      (libsource (lib "*") (part "RESISTOR_Dup1"))
    )
    (comp (ref "R8311")
      (value "*")
      (footprint "R0402")
      (description "НЁУГєсД¤µзЧи,0R,+/-5%,R0603,1/10W.")
      (fields
        (field (name "PCB FOOTPRINT") "R0603")
        (field (name "TOLERANCE") "5%")
        (field (name "MANUFACTURER") "YAGEO")
        (field (name "ALTIUM_UNNAMED_1") "0R")
        (field (name "CREATED BY") "YTL")
      )
      (libsource (lib "*") (part "RESISTOR_Dup1"))
    )
    (comp (ref "R8312")
      (value "*")
      (footprint "R0402")
      (description "НЁУГєсД¤µзЧи,0R,+/-5%,R0603,1/10W.")
      (fields
        (field (name "PCB FOOTPRINT") "R0603")
        (field (name "TOLERANCE") "5%")
        (field (name "MANUFACTURER") "YAGEO")
        (field (name "ALTIUM_UNNAMED_1") "0R")
        (field (name "CREATED BY") "YTL")
      )
      (libsource (lib "*") (part "RESISTOR_Dup1"))
    )
    (comp (ref "TP8300")
      (value "*")
      (footprint "TEST")
      (description "Test Point 0.7mm")
      (fields (field (name "ALTIUM_UNNAMED_1") "TP_0.7") (field (name "CREATED BY") "JJJ"))
      (libsource (lib "*") (part "TP"))
    )
    (comp (ref "TP8301")
      (value "*")
      (footprint "TEST")
      (description "Test Point 0.7mm")
      (fields (field (name "ALTIUM_UNNAMED_1") "TP_0.7") (field (name "CREATED BY") "JJJ"))
      (libsource (lib "*") (part "TP"))
    )
    (comp (ref "U8300")
      (value "*")
      (footprint "QFN64")
      (fields
        (field (name "PCB FOOTPRINT") "QFN64_9R00X9R00X0R90_T")
        (field (name "ALTIUM_UNNAMED_1") "JMB575")
      )
      (libsource (lib "*") (part "JMB575"))
    )
    (comp (ref "U8301")
      (value "*")
      (footprint "WSON8_8R00X6R00X0R80_T")
      (description "256M-bit Serial Flash;32M-byte;3.3V Uniform Sector;Dual and Quad Serial Flash;")
      (fields
        (field (name "PCB FOOTPRINT") "WSON8_8R00X6R00X0R80_T")
        (field (name "MANUFACTURER") "GigaDevice")
        (field (name "ALTIUM_UNNAMED_1") "W25X40CLNIG/SOIC-8")
        (field (name "CREATED BY") "JJJ")
      )
      (libsource (lib "*") (part "SPI_FLASH_8PIN_T_0"))
    )
    (comp (ref "Y8300")
      (value "*")
      (footprint "CRY-3225")
      (description "ОЮФґѕ§ХсЈ¬25MЈ¬3225,ЎА10ppmЈ¬10pFЈ¬Hosonic")
      (fields
        (field (name "PCB FOOTPRINT") "CRY4_3R20X2R50X0R80")
        (field (name "MANUFACTURER") "Hosonic(єиРЗµзЧУ)")
        (field (name "ALTIUM_UNNAMED_1") "25MHz")
        (field (name "CREATED BY") "JJJ")
      )
      (libsource (lib "*") (part "CRYSTAL_4P"))
    )
  )
  (nets
    (net (code "1") (name "/SATAPM1_GPIO0") (class "Default")
      (node (ref "U8300") (pin "17") (pinfunction "ZGPIO00_17") (pintype "passive"))
      (node (ref "U8301") (pin "6") (pinfunction "CLK_6") (pintype "passive"))
    )
    (net (code "2") (name "/SATAPM1_GPIO1") (class "Default")
      (node (ref "U8300") (pin "16") (pinfunction "ZGPIO01_16") (pintype "passive"))
      (node (ref "U8301") (pin "5") (pinfunction "DI(D0)_5") (pintype "passive"))
    )
    (net (code "3") (name "/SATAPM1_GPIO2") (class "Default")
      (node (ref "U8300") (pin "15") (pinfunction "ZGPIO02_15") (pintype "passive"))
      (node (ref "U8301") (pin "2") (pinfunction "DO(D1)_2") (pintype "passive"))
    )
    (net (code "4") (name "/SATAPM1_GPIO3") (class "Default")
      (node (ref "R8304") (pin "2") (pinfunction "2_2") (pintype "passive"))
      (node (ref "U8300") (pin "11") (pinfunction "ZGPIO03_11") (pintype "passive"))
      (node (ref "U8301") (pin "3") (pinfunction "~{WP}(D2)_3") (pintype "passive"))
    )
    (net (code "5") (name "/SATAPM1_GPIO4") (class "Default")
      (node (ref "R8305") (pin "2") (pinfunction "2_2") (pintype "passive"))
      (node (ref "U8300") (pin "10") (pinfunction "ZGPIO04_10") (pintype "passive"))
      (node (ref "U8301") (pin "7") (pinfunction "~{HOLD}(D3)_7") (pintype "passive"))
    )
    (net (code "6") (name "/SATAPM1_GPIO12") (class "Default")
      (node (ref "R8302") (pin "2") (pinfunction "2_2") (pintype "passive"))
      (node (ref "TP8300") (pin "1") (pinfunction "1_1") (pintype "passive"))
      (node (ref "U8300") (pin "63") (pinfunction "ZGPIO12_63") (pintype "passive"))
    )
    (net (code "7") (name "/SATAPM1_GPIO13") (class "Default")
      (node (ref "R8309") (pin "2") (pinfunction "2_2") (pintype "passive"))
      (node (ref "TP8301") (pin "1") (pinfunction "1_1") (pintype "passive"))
      (node (ref "U8300") (pin "19") (pinfunction "ZGPIO13_19") (pintype "passive"))
    )
    (net (code "8") (name "/SATAPM1_GPIO14") (class "Default")
      (node (ref "R8303") (pin "2") (pinfunction "2_2") (pintype "passive"))
      (node (ref "R8308") (pin "2") (pinfunction "2_2") (pintype "passive"))
      (node (ref "U8300") (pin "18") (pinfunction "ZGPIO14_18") (pintype "passive"))
      (node (ref "U8301") (pin "1") (pinfunction "~{CS}_1") (pintype "passive"))
    )
    (net (code "9") (name "/SATAPM1_REXT") (class "Default")
      (node (ref "R8306") (pin "1") (pinfunction "1_1") (pintype "passive"))
      (node (ref "U8300") (pin "42") (pinfunction "AREXT_42") (pintype "passive"))
    )
    (net (code "10") (name "/SATAPM1_RSTn") (class "Default")
      (node (ref "C8304") (pin "1") (pinfunction "1_1") (pintype "passive"))
      (node (ref "R8300") (pin "2") (pinfunction "2_2") (pintype "passive"))
      (node (ref "R8301") (pin "2") (pinfunction "2_2") (pintype "passive"))
      (node (ref "U8300") (pin "62") (pinfunction "XRSTN_62") (pintype "passive"))
    )
    (net (code "11") (name "/SATAPM1_RXN0") (class "Default")
      (node (ref "C8317") (pin "1") (pinfunction "1_1") (pintype "passive"))
      (node (ref "U8300") (pin "45") (pinfunction "ARXN0_45") (pintype "passive"))
    )
    (net (code "12") (name "/SATAPM1_RXN1") (class "Default")
      (node (ref "C8302") (pin "1") (pinfunction "1_1") (pintype "passive"))
      (node (ref "U8300") (pin "57") (pinfunction "ARXN1_57") (pintype "passive"))
    )
    (net (code "13") (name "/SATAPM1_RXN2") (class "Default")
      (node (ref "C8307") (pin "1") (pinfunction "1_1") (pintype "passive"))
      (node (ref "U8300") (pin "51") (pinfunction "ARXN2_51") (pintype "passive"))
    )
    (net (code "14") (name "/SATAPM1_RXN3") (class "Default")
      (node (ref "C8322") (pin "1") (pinfunction "1_1") (pintype "passive"))
      (node (ref "U8300") (pin "34") (pinfunction "ARXN3_34") (pintype "passive"))
    )
    (net (code "15") (name "/SATAPM1_RXN4") (class "Default")
      (node (ref "C8337") (pin "1") (pinfunction "1_1") (pintype "passive"))
      (node (ref "U8300") (pin "28") (pinfunction "ARXN4_28") (pintype "passive"))
    )
    (net (code "16") (name "/SATAPM1_RXN5") (class "Default")
      (node (ref "C8312") (pin "2") (pinfunction "2_2") (pintype "passive"))
      (node (ref "U8300") (pin "22") (pinfunction "ARXN5_22") (pintype "passive"))
    )
    (net (code "17") (name "/SATAPM1_RXN_0") (class "Default")
      (node (ref "C8317") (pin "2") (pinfunction "2_2") (pintype "passive"))
      (node (ref "J8302") (pin "5") (pinfunction "RXN_5") (pintype "passive"))
    )
    (net (code "18") (name "/SATAPM1_RXN_1") (class "Default")
      (node (ref "C8302") (pin "2") (pinfunction "2_2") (pintype "passive"))
      (node (ref "J8300") (pin "5") (pinfunction "RXN_5") (pintype "passive"))
    )
    (net (code "19") (name "/SATAPM1_RXN_2") (class "Default")
      (node (ref "C8307") (pin "2") (pinfunction "2_2") (pintype "passive"))
      (node (ref "J8301") (pin "5") (pinfunction "RXN_5") (pintype "passive"))
    )
    (net (code "20") (name "/SATAPM1_RXN_3") (class "Default")
      (node (ref "C8322") (pin "2") (pinfunction "2_2") (pintype "passive"))
      (node (ref "J8303") (pin "5") (pinfunction "RXN_5") (pintype "passive"))
    )
    (net (code "21") (name "/SATAPM1_RXN_4") (class "Default")
      (node (ref "C8337") (pin "2") (pinfunction "2_2") (pintype "passive"))
      (node (ref "J8304") (pin "5") (pinfunction "RXN_5") (pintype "passive"))
    )
    (net (code "22") (name "/SATAPM1_RXP0") (class "Default")
      (node (ref "C8319") (pin "1") (pinfunction "1_1") (pintype "passive"))
      (node (ref "U8300") (pin "44") (pinfunction "ARXP0_44") (pintype "passive"))
    )
    (net (code "23") (name "/SATAPM1_RXP1") (class "Default")
      (node (ref "C8303") (pin "1") (pinfunction "1_1") (pintype "passive"))
      (node (ref "U8300") (pin "56") (pinfunction "ARXP1_56") (pintype "passive"))
    )
    (net (code "24") (name "/SATAPM1_RXP2") (class "Default")
      (node (ref "C8309") (pin "1") (pinfunction "1_1") (pintype "passive"))
      (node (ref "U8300") (pin "50") (pinfunction "ARXP2_50") (pintype "passive"))
    )
    (net (code "25") (name "/SATAPM1_RXP3") (class "Default")
      (node (ref "C8323") (pin "1") (pinfunction "1_1") (pintype "passive"))
      (node (ref "U8300") (pin "33") (pinfunction "ARXP3_33") (pintype "passive"))
    )
    (net (code "26") (name "/SATAPM1_RXP4") (class "Default")
      (node (ref "C8338") (pin "1") (pinfunction "1_1") (pintype "passive"))
      (node (ref "U8300") (pin "27") (pinfunction "ARXP4_27") (pintype "passive"))
    )
    (net (code "27") (name "/SATAPM1_RXP5") (class "Default")
      (node (ref "C8310") (pin "2") (pinfunction "2_2") (pintype "passive"))
      (node (ref "U8300") (pin "21") (pinfunction "ARXP5_21") (pintype "passive"))
    )
    (net (code "28") (name "/SATAPM1_RXP_0") (class "Default")
      (node (ref "C8319") (pin "2") (pinfunction "2_2") (pintype "passive"))
      (node (ref "J8302") (pin "6") (pinfunction "RXP_6") (pintype "passive"))
    )
    (net (code "29") (name "/SATAPM1_RXP_1") (class "Default")
      (node (ref "C8303") (pin "2") (pinfunction "2_2") (pintype "passive"))
      (node (ref "J8300") (pin "6") (pinfunction "RXP_6") (pintype "passive"))
    )
    (net (code "30") (name "/SATAPM1_RXP_2") (class "Default")
      (node (ref "C8309") (pin "2") (pinfunction "2_2") (pintype "passive"))
      (node (ref "J8301") (pin "6") (pinfunction "RXP_6") (pintype "passive"))
    )
    (net (code "31") (name "/SATAPM1_RXP_3") (class "Default")
      (node (ref "C8323") (pin "2") (pinfunction "2_2") (pintype "passive"))
      (node (ref "J8303") (pin "6") (pinfunction "RXP_6") (pintype "passive"))
    )
    (net (code "32") (name "/SATAPM1_RXP_4") (class "Default")
      (node (ref "C8338") (pin "2") (pinfunction "2_2") (pintype "passive"))
      (node (ref "J8304") (pin "6") (pinfunction "RXP_6") (pintype "passive"))
    )
    (net (code "33") (name "/SATAPM1_TESTn") (class "Default")
      (node (ref "R8310") (pin "2") (pinfunction "2_2") (pintype "passive"))
      (node (ref "U8300") (pin "20") (pinfunction "XTSTN_20") (pintype "passive"))
    )
    (net (code "34") (name "/SATAPM1_TXN0") (class "Default")
      (node (ref "C8315") (pin "1") (pinfunction "1_1") (pintype "passive"))
      (node (ref "U8300") (pin "47") (pinfunction "ATXN0_47") (pintype "passive"))
    )
    (net (code "35") (name "/SATAPM1_TXN1") (class "Default")
      (node (ref "C8301") (pin "1") (pinfunction "1_1") (pintype "passive"))
      (node (ref "U8300") (pin "59") (pinfunction "ATXN1_59") (pintype "passive"))
    )
    (net (code "36") (name "/SATAPM1_TXN2") (class "Default")
      (node (ref "C8306") (pin "1") (pinfunction "1_1") (pintype "passive"))
      (node (ref "U8300") (pin "53") (pinfunction "ATXN2_53") (pintype "passive"))
    )
    (net (code "37") (name "/SATAPM1_TXN3") (class "Default")
      (node (ref "C8321") (pin "1") (pinfunction "1_1") (pintype "passive"))
      (node (ref "U8300") (pin "36") (pinfunction "ATXN3_36") (pintype "passive"))
    )
    (net (code "38") (name "/SATAPM1_TXN4") (class "Default")
      (node (ref "C8336") (pin "1") (pinfunction "1_1") (pintype "passive"))
      (node (ref "U8300") (pin "30") (pinfunction "ATXN4_30") (pintype "passive"))
    )
    (net (code "39") (name "/SATAPM1_TXN5") (class "Default")
      (node (ref "C8316") (pin "2") (pinfunction "2_2") (pintype "passive"))
      (node (ref "U8300") (pin "24") (pinfunction "ATXN5_24") (pintype "passive"))
    )
    (net (code "40") (name "/SATAPM1_TXN_0") (class "Default")
      (node (ref "C8315") (pin "2") (pinfunction "2_2") (pintype "passive"))
      (node (ref "J8302") (pin "3") (pinfunction "TXN_3") (pintype "passive"))
    )
    (net (code "41") (name "/SATAPM1_TXN_1") (class "Default")
      (node (ref "C8301") (pin "2") (pinfunction "2_2") (pintype "passive"))
      (node (ref "J8300") (pin "3") (pinfunction "TXN_3") (pintype "passive"))
    )
    (net (code "42") (name "/SATAPM1_TXN_2") (class "Default")
      (node (ref "C8306") (pin "2") (pinfunction "2_2") (pintype "passive"))
      (node (ref "J8301") (pin "3") (pinfunction "TXN_3") (pintype "passive"))
    )
    (net (code "43") (name "/SATAPM1_TXN_3") (class "Default")
      (node (ref "C8321") (pin "2") (pinfunction "2_2") (pintype "passive"))
      (node (ref "J8303") (pin "3") (pinfunction "TXN_3") (pintype "passive"))
    )
    (net (code "44") (name "/SATAPM1_TXN_4") (class "Default")
      (node (ref "C8336") (pin "2") (pinfunction "2_2") (pintype "passive"))
      (node (ref "J8304") (pin "3") (pinfunction "TXN_3") (pintype "passive"))
    )
    (net (code "45") (name "/SATAPM1_TXP0") (class "Default")
      (node (ref "C8314") (pin "1") (pinfunction "1_1") (pintype "passive"))
      (node (ref "U8300") (pin "48") (pinfunction "ATXP0_48") (pintype "passive"))
    )
    (net (code "46") (name "/SATAPM1_TXP1") (class "Default")
      (node (ref "C8300") (pin "1") (pinfunction "1_1") (pintype "passive"))
      (node (ref "U8300") (pin "60") (pinfunction "ATXP1_60") (pintype "passive"))
    )
    (net (code "47") (name "/SATAPM1_TXP2") (class "Default")
      (node (ref "C8305") (pin "1") (pinfunction "1_1") (pintype "passive"))
      (node (ref "U8300") (pin "54") (pinfunction "ATXP2_54") (pintype "passive"))
    )
    (net (code "48") (name "/SATAPM1_TXP3") (class "Default")
      (node (ref "C8320") (pin "1") (pinfunction "1_1") (pintype "passive"))
      (node (ref "U8300") (pin "37") (pinfunction "ATXP3_37") (pintype "passive"))
    )
    (net (code "49") (name "/SATAPM1_TXP4") (class "Default")
      (node (ref "C8335") (pin "1") (pinfunction "1_1") (pintype "passive"))
      (node (ref "U8300") (pin "31") (pinfunction "ATXP4_31") (pintype "passive"))
    )
    (net (code "50") (name "/SATAPM1_TXP5") (class "Default")
      (node (ref "C8318") (pin "2") (pinfunction "2_2") (pintype "passive"))
      (node (ref "U8300") (pin "25") (pinfunction "ATXP5_25") (pintype "passive"))
    )
    (net (code "51") (name "/SATAPM1_TXP_0") (class "Default")
      (node (ref "C8314") (pin "2") (pinfunction "2_2") (pintype "passive"))
      (node (ref "J8302") (pin "2") (pinfunction "TXP_2") (pintype "passive"))
    )
    (net (code "52") (name "/SATAPM1_TXP_1") (class "Default")
      (node (ref "C8300") (pin "2") (pinfunction "2_2") (pintype "passive"))
      (node (ref "J8300") (pin "2") (pinfunction "TXP_2") (pintype "passive"))
    )
    (net (code "53") (name "/SATAPM1_TXP_2") (class "Default")
      (node (ref "C8305") (pin "2") (pinfunction "2_2") (pintype "passive"))
      (node (ref "J8301") (pin "2") (pinfunction "TXP_2") (pintype "passive"))
    )
    (net (code "54") (name "/SATAPM1_TXP_3") (class "Default")
      (node (ref "C8320") (pin "2") (pinfunction "2_2") (pintype "passive"))
      (node (ref "J8303") (pin "2") (pinfunction "TXP_2") (pintype "passive"))
    )
    (net (code "55") (name "/SATAPM1_TXP_4") (class "Default")
      (node (ref "C8335") (pin "2") (pinfunction "2_2") (pintype "passive"))
      (node (ref "J8304") (pin "2") (pinfunction "TXP_2") (pintype "passive"))
    )
    (net (code "56") (name "/SATAPM1_XIN") (class "Default")
      (node (ref "C8313") (pin "1") (pinfunction "1_1") (pintype "passive"))
      (node (ref "R8307") (pin "2") (pinfunction "2_2") (pintype "passive"))
      (node (ref "U8300") (pin "39") (pinfunction "AXIN_39") (pintype "passive"))
      (node (ref "Y8300") (pin "3") (pinfunction "X2_3") (pintype "passive"))
    )
    (net (code "57") (name "/SATAPM1_XOUT") (class "Default")
      (node (ref "C8311") (pin "1") (pinfunction "1_1") (pintype "passive"))
      (node (ref "R8307") (pin "1") (pinfunction "1_1") (pintype "passive"))
      (node (ref "U8300") (pin "40") (pinfunction "AXOUT_40") (pintype "passive"))
      (node (ref "Y8300") (pin "1") (pinfunction "X1_1") (pintype "passive"))
    )
    (net (code "58") (name "GND") (class "Default")
      (node (ref "C8304") (pin "2") (pinfunction "2_2") (pintype "passive"))
      (node (ref "C8308") (pin "2") (pinfunction "2_2") (pintype "passive"))
      (node (ref "C8311") (pin "2") (pinfunction "2_2") (pintype "passive"))
      (node (ref "C8313") (pin "2") (pinfunction "2_2") (pintype "passive"))
      (node (ref "C8324") (pin "2") (pinfunction "2_2") (pintype "passive"))
      (node (ref "C8325") (pin "2") (pinfunction "2_2") (pintype "passive"))
      (node (ref "C8326") (pin "2") (pinfunction "2_2") (pintype "passive"))
      (node (ref "C8327") (pin "2") (pinfunction "2_2") (pintype "passive"))
      (node (ref "C8328") (pin "2") (pinfunction "2_2") (pintype "passive"))
      (node (ref "C8329") (pin "2") (pinfunction "2_2") (pintype "passive"))
      (node (ref "C8330") (pin "2") (pinfunction "2_2") (pintype "passive"))
      (node (ref "C8331") (pin "2") (pinfunction "2_2") (pintype "passive"))
      (node (ref "C8332") (pin "2") (pinfunction "2_2") (pintype "passive"))
      (node (ref "C8333") (pin "2") (pinfunction "2_2") (pintype "passive"))
      (node (ref "C8334") (pin "2") (pinfunction "2_2") (pintype "passive"))
      (node (ref "C8339") (pin "2") (pinfunction "2_2") (pintype "passive"))
      (node (ref "C8340") (pin "2") (pinfunction "2_2") (pintype "passive"))
      (node (ref "C8341") (pin "2") (pinfunction "2_2") (pintype "passive"))
      (node (ref "C8342") (pin "2") (pinfunction "2_2") (pintype "passive"))
      (node (ref "C8343") (pin "2") (pinfunction "2_2") (pintype "passive"))
      (node (ref "C8344") (pin "2") (pinfunction "2_2") (pintype "passive"))
      (node (ref "C8345") (pin "2") (pinfunction "2_2") (pintype "passive"))
      (node (ref "C8346") (pin "2") (pinfunction "2_2") (pintype "passive"))
      (node (ref "C8347") (pin "2") (pinfunction "2_2") (pintype "passive"))
      (node (ref "C8348") (pin "2") (pinfunction "2_2") (pintype "passive"))
      (node (ref "C8349") (pin "2") (pinfunction "2_2") (pintype "passive"))
      (node (ref "J8300") (pin "1") (pinfunction "GND1_1") (pintype "passive"))
      (node (ref "J8300") (pin "4") (pinfunction "GND2_4") (pintype "passive"))
      (node (ref "J8300") (pin "7") (pinfunction "GND3_7") (pintype "passive"))
      (node (ref "J8300") (pin "8") (pinfunction "GND4_8") (pintype "passive"))
      (node (ref "J8300") (pin "9") (pinfunction "GND5_9") (pintype "passive"))
      (node (ref "J8301") (pin "1") (pinfunction "GND1_1") (pintype "passive"))
      (node (ref "J8301") (pin "4") (pinfunction "GND2_4") (pintype "passive"))
      (node (ref "J8301") (pin "7") (pinfunction "GND3_7") (pintype "passive"))
      (node (ref "J8301") (pin "8") (pinfunction "GND4_8") (pintype "passive"))
      (node (ref "J8301") (pin "9") (pinfunction "GND5_9") (pintype "passive"))
      (node (ref "J8302") (pin "1") (pinfunction "GND1_1") (pintype "passive"))
      (node (ref "J8302") (pin "4") (pinfunction "GND2_4") (pintype "passive"))
      (node (ref "J8302") (pin "7") (pinfunction "GND3_7") (pintype "passive"))
      (node (ref "J8302") (pin "8") (pinfunction "GND4_8") (pintype "passive"))
      (node (ref "J8302") (pin "9") (pinfunction "GND5_9") (pintype "passive"))
      (node (ref "J8303") (pin "1") (pinfunction "GND1_1") (pintype "passive"))
      (node (ref "J8303") (pin "4") (pinfunction "GND2_4") (pintype "passive"))
      (node (ref "J8303") (pin "7") (pinfunction "GND3_7") (pintype "passive"))
      (node (ref "J8303") (pin "8") (pinfunction "GND4_8") (pintype "passive"))
      (node (ref "J8303") (pin "9") (pinfunction "GND5_9") (pintype "passive"))
      (node (ref "J8304") (pin "1") (pinfunction "GND1_1") (pintype "passive"))
      (node (ref "J8304") (pin "4") (pinfunction "GND2_4") (pintype "passive"))
      (node (ref "J8304") (pin "7") (pinfunction "GND3_7") (pintype "passive"))
      (node (ref "J8304") (pin "8") (pinfunction "GND4_8") (pintype "passive"))
      (node (ref "J8304") (pin "9") (pinfunction "GND5_9") (pintype "passive"))
      (node (ref "R8302") (pin "1") (pinfunction "1_1") (pintype "passive"))
      (node (ref "R8306") (pin "2") (pinfunction "2_2") (pintype "passive"))
      (node (ref "U8300") (pin "13") (pinfunction "DGND_2_13") (pintype "passive"))
      (node (ref "U8300") (pin "41") (pinfunction "AGNDC_41") (pintype "passive"))
      (node (ref "U8300") (pin "5") (pinfunction "DGND_1_5") (pintype "passive"))
      (node (ref "U8300") (pin "65") (pinfunction "EPAD_65") (pintype "passive"))
      (node (ref "U8301") (pin "4") (pinfunction "VSS_4") (pintype "passive"))
      (node (ref "U8301") (pin "9") (pinfunction "EPAD_9") (pintype "passive"))
      (node (ref "Y8300") (pin "2") (pinfunction "GND_2") (pintype "power_in"))
      (node (ref "Y8300") (pin "4") (pinfunction "GND_4") (pintype "power_in"))
    )
    (net (code "59") (name "SATA30_1_RXN") (class "Default")
      (node (ref "C8316") (pin "1") (pinfunction "1_1") (pintype "passive"))
    )
    (net (code "60") (name "SATA30_1_RXP") (class "Default")
      (node (ref "C8318") (pin "1") (pinfunction "1_1") (pintype "passive"))
    )
    (net (code "61") (name "SATA30_1_TXN") (class "Default")
      (node (ref "C8312") (pin "1") (pinfunction "1_1") (pintype "passive"))
    )
    (net (code "62") (name "SATA30_1_TXP") (class "Default")
      (node (ref "C8310") (pin "1") (pinfunction "1_1") (pintype "passive"))
    )
    (net (code "63") (name "SATAPM1_RSTn_L_GPIO4_A1") (class "Default")
      (node (ref "R8301") (pin "1") (pinfunction "1_1") (pintype "passive"))
    )
    (net (code "64") (name "VCC3V3_SATAPM0") (class "Default")
      (node (ref "R8311") (pin "1") (pinfunction "1_1") (pintype "passive"))
    )
    (net (code "65") (name "VCC3V3_SATAPM1") (class "Default")
      (node (ref "C8308") (pin "1") (pinfunction "1_1") (pintype "passive"))
      (node (ref "C8324") (pin "1") (pinfunction "1_1") (pintype "passive"))
      (node (ref "C8325") (pin "1") (pinfunction "1_1") (pintype "passive"))
      (node (ref "C8326") (pin "1") (pinfunction "1_1") (pintype "passive"))
      (node (ref "C8327") (pin "1") (pinfunction "1_1") (pintype "passive"))
      (node (ref "C8328") (pin "1") (pinfunction "1_1") (pintype "passive"))
      (node (ref "C8329") (pin "1") (pinfunction "1_1") (pintype "passive"))
      (node (ref "C8330") (pin "1") (pinfunction "1_1") (pintype "passive"))
      (node (ref "C8331") (pin "1") (pinfunction "1_1") (pintype "passive"))
      (node (ref "C8332") (pin "1") (pinfunction "1_1") (pintype "passive"))
      (node (ref "C8333") (pin "1") (pinfunction "1_1") (pintype "passive"))
      (node (ref "C8334") (pin "1") (pinfunction "1_1") (pintype "passive"))
      (node (ref "R8300") (pin "1") (pinfunction "1_1") (pintype "passive"))
      (node (ref "R8303") (pin "1") (pinfunction "1_1") (pintype "passive"))
      (node (ref "R8304") (pin "1") (pinfunction "1_1") (pintype "passive"))
      (node (ref "R8305") (pin "1") (pinfunction "1_1") (pintype "passive"))
      (node (ref "R8308") (pin "1") (pinfunction "1_1") (pintype "passive"))
      (node (ref "R8309") (pin "1") (pinfunction "1_1") (pintype "passive"))
      (node (ref "R8310") (pin "1") (pinfunction "1_1") (pintype "passive"))
      (node (ref "R8311") (pin "2") (pinfunction "2_2") (pintype "passive"))
      (node (ref "U8300") (pin "12") (pinfunction "DV33_2_12") (pintype "passive"))
      (node (ref "U8300") (pin "26") (pinfunction "AV33_5_26") (pintype "passive"))
      (node (ref "U8300") (pin "32") (pinfunction "AV33_4_32") (pintype "passive"))
      (node (ref "U8300") (pin "38") (pinfunction "AV33_3_38") (pintype "passive"))
      (node (ref "U8300") (pin "43") (pinfunction "AV33_C_43") (pintype "passive"))
      (node (ref "U8300") (pin "49") (pinfunction "AV33_0_49") (pintype "passive"))
      (node (ref "U8300") (pin "55") (pinfunction "AV33_2_55") (pintype "passive"))
      (node (ref "U8300") (pin "6") (pinfunction "DV33_1_6") (pintype "passive"))
      (node (ref "U8300") (pin "61") (pinfunction "AV33_1_61") (pintype "passive"))
      (node (ref "U8301") (pin "8") (pinfunction "VCC_8") (pintype "passive"))
    )
    (net (code "66") (name "VDD1V2_SATAPM0") (class "Default")
      (node (ref "R8312") (pin "1") (pinfunction "1_1") (pintype "passive"))
    )
    (net (code "67") (name "VDD1V2_SATAPM1") (class "Default")
      (node (ref "C8339") (pin "1") (pinfunction "1_1") (pintype "passive"))
      (node (ref "C8340") (pin "1") (pinfunction "1_1") (pintype "passive"))
      (node (ref "C8341") (pin "1") (pinfunction "1_1") (pintype "passive"))
      (node (ref "C8342") (pin "1") (pinfunction "1_1") (pintype "passive"))
      (node (ref "C8343") (pin "1") (pinfunction "1_1") (pintype "passive"))
      (node (ref "C8344") (pin "1") (pinfunction "1_1") (pintype "passive"))
      (node (ref "C8345") (pin "1") (pinfunction "1_1") (pintype "passive"))
      (node (ref "C8346") (pin "1") (pinfunction "1_1") (pintype "passive"))
      (node (ref "C8347") (pin "1") (pinfunction "1_1") (pintype "passive"))
      (node (ref "C8348") (pin "1") (pinfunction "1_1") (pintype "passive"))
      (node (ref "C8349") (pin "1") (pinfunction "1_1") (pintype "passive"))
      (node (ref "R8312") (pin "2") (pinfunction "2_2") (pintype "passive"))
      (node (ref "U8300") (pin "14") (pinfunction "DV12_2_14") (pintype "passive"))
      (node (ref "U8300") (pin "23") (pinfunction "AV12_5_23") (pintype "passive"))
      (node (ref "U8300") (pin "29") (pinfunction "AV12_4_29") (pintype "passive"))
      (node (ref "U8300") (pin "35") (pinfunction "AV12_3_35") (pintype "passive"))
      (node (ref "U8300") (pin "4") (pinfunction "DV12_1_4") (pintype "passive"))
      (node (ref "U8300") (pin "46") (pinfunction "AV12_0_46") (pintype "passive"))
      (node (ref "U8300") (pin "52") (pinfunction "AV12_2_52") (pintype "passive"))
      (node (ref "U8300") (pin "58") (pinfunction "AV12_1_58") (pintype "passive"))
    )
    (net (code "68") (name "unconnected-(U8300-ZGPIO05-Pad9)") (class "Default")
      (node (ref "U8300") (pin "9") (pinfunction "ZGPIO05_9") (pintype "passive+no_connect"))
    )
    (net (code "69") (name "unconnected-(U8300-ZGPIO06-Pad8)") (class "Default")
      (node (ref "U8300") (pin "8") (pinfunction "ZGPIO06_8") (pintype "passive+no_connect"))
    )
    (net (code "70") (name "unconnected-(U8300-ZGPIO07-Pad7)") (class "Default")
      (node (ref "U8300") (pin "7") (pinfunction "ZGPIO07_7") (pintype "passive+no_connect"))
    )
    (net (code "71") (name "unconnected-(U8300-ZGPIO08-Pad3)") (class "Default")
      (node (ref "U8300") (pin "3") (pinfunction "ZGPIO08_3") (pintype "passive+no_connect"))
    )
    (net (code "72") (name "unconnected-(U8300-ZGPIO09-Pad2)") (class "Default")
      (node (ref "U8300") (pin "2") (pinfunction "ZGPIO09_2") (pintype "passive+no_connect"))
    )
    (net (code "73") (name "unconnected-(U8300-ZGPIO10-Pad1)") (class "Default")
      (node (ref "U8300") (pin "1") (pinfunction "ZGPIO10_1") (pintype "passive+no_connect"))
    )
    (net (code "74") (name "unconnected-(U8300-ZGPIO11-Pad64)") (class "Default")
      (node (ref "U8300") (pin "64") (pinfunction "ZGPIO11_64") (pintype "passive+no_connect"))
    )
  )
)
